# board.net
KiCad netlist of a schematic drawn in EAGLE
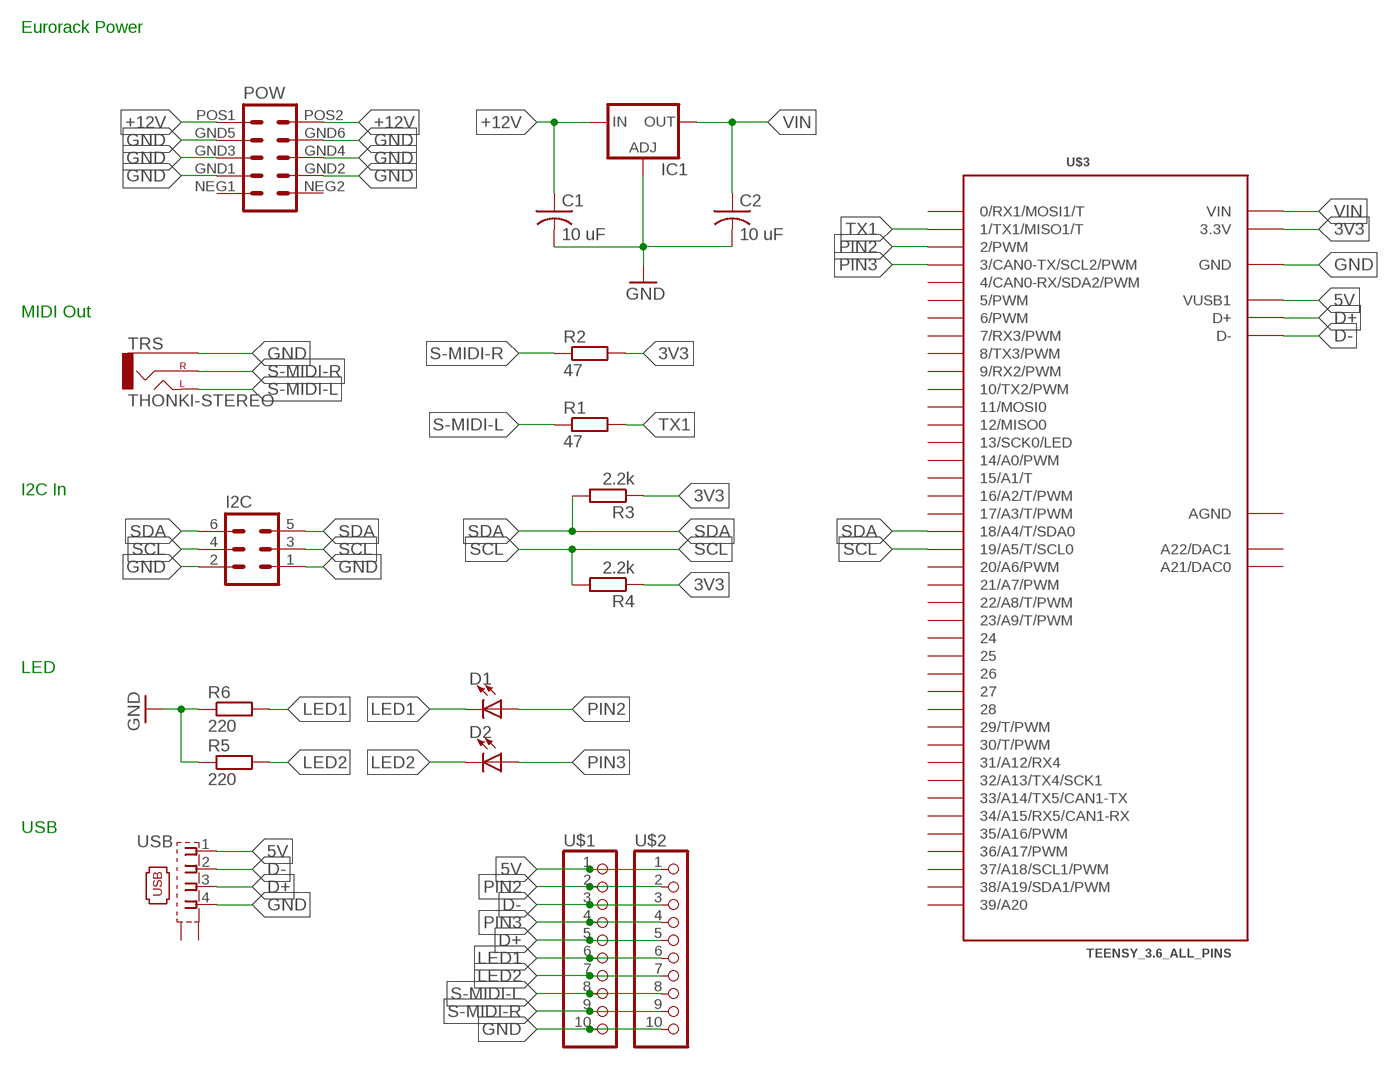
[diagram p0: schematic, sheet 1]

(export (version "E")
  (design (tool "Eeschema 10.0.6"))
  (components
    (comp (ref "C1")
      (value "10 uF")
      (footprint "eagle-import:C050-025X075")
      (libsource (lib "eagle-import") (part "C-US050-025X075"))
    )
    (comp (ref "C2")
      (value "10 uF")
      (footprint "eagle-import:C050-025X075")
      (libsource (lib "eagle-import") (part "C-US050-025X075"))
    )
    (comp (ref "D1")
      (value "LED3MM")
      (footprint "eagle-import:LED3MM")
      (libsource (lib "eagle-import") (part "LED3MM"))
    )
    (comp (ref "D2")
      (value "LED3MM")
      (footprint "eagle-import:LED3MM")
      (libsource (lib "eagle-import") (part "LED3MM"))
    )
    (comp (ref "I2C")
      (value "MA03-2BACKSIDEFRONTSIDE")
      (footprint "eagle-import:MA03-2")
      (libsource (lib "eagle-import") (part "MA03-2BACKSIDEFRONTSIDE"))
    )
    (comp (ref "IC1")
      (value "LD117AS50TR")
      (footprint "eagle-import:SOT223")
      (libsource (lib "eagle-import") (part "LD117A?S50TR"))
    )
    (comp (ref "POW")
      (value "EURO_POWER_HEADERLOCK_PADS")
      (footprint "eagle-import:EURO_PWR_HEADER_LOCK")
      (libsource (lib "eagle-import") (part "EURO_POWER_HEADERLOCK_PADS"))
    )
    (comp (ref "R1")
      (value "47")
      (footprint "eagle-import:10MM_RESISTOR")
      (libsource (lib "eagle-import") (part "RESISTOR10MM_RESISTOR"))
    )
    (comp (ref "R2")
      (value "47")
      (footprint "eagle-import:10MM_RESISTOR")
      (libsource (lib "eagle-import") (part "RESISTOR10MM_RESISTOR"))
    )
    (comp (ref "R3")
      (value "2.2k")
      (footprint "eagle-import:10MM_RESISTOR")
      (libsource (lib "eagle-import") (part "RESISTOR10MM_RESISTOR"))
    )
    (comp (ref "R4")
      (value "2.2k")
      (footprint "eagle-import:10MM_RESISTOR")
      (libsource (lib "eagle-import") (part "RESISTOR10MM_RESISTOR"))
    )
    (comp (ref "R5")
      (value "220")
      (footprint "eagle-import:10MM_RESISTOR")
      (libsource (lib "eagle-import") (part "RESISTOR10MM_RESISTOR"))
    )
    (comp (ref "R6")
      (value "220")
      (footprint "eagle-import:10MM_RESISTOR")
      (libsource (lib "eagle-import") (part "RESISTOR10MM_RESISTOR"))
    )
    (comp (ref "TRS")
      (value "THONKI-STEREO")
      (footprint "eagle-import:WQP-PJ366ST_JACK")
      (libsource (lib "eagle-import") (part "THONKI-STEREO"))
    )
    (comp (ref "U$1")
      (value "PINHD-1X10")
      (footprint "eagle-import:1X10-BIG")
      (libsource (lib "eagle-import") (part "PINHD-1X10"))
    )
    (comp (ref "U$2")
      (value "PINHD-1X10")
      (footprint "eagle-import:1X10-BIG")
      (libsource (lib "eagle-import") (part "PINHD-1X10"))
    )
    (comp (ref "U$3")
      (value "TEENSY_3.6_ALL_PINS")
      (footprint "eagle-import:TEENSY_3.6_ALL_PINS")
      (libsource (lib "eagle-import") (part "TEENSY_3.6_ALL_PINS"))
    )
    (comp (ref "USB")
      (value "KUSBVX")
      (footprint "eagle-import:KUSBVX")
      (libsource (lib "eagle-import") (part "KUSBVX"))
    )
  )
  (nets
    (net (code "1") (name "+12V") (class "Default")
      (node (ref "C1") (pin "1") (pinfunction "1_1") (pintype "passive"))
      (node (ref "IC1") (pin "3") (pinfunction "IN_3") (pintype "input"))
      (node (ref "POW") (pin "POS1") (pinfunction "10_POS1") (pintype "passive"))
      (node (ref "POW") (pin "POS2") (pinfunction "9_POS2") (pintype "passive"))
    )
    (net (code "2") (name "/AGND") (class "Default")
      (node (ref "U$3") (pin "AGND") (pinfunction "AGND_AGND") (pintype "power_in"))
    )
    (net (code "3") (name "3V3") (class "Default")
      (node (ref "R2") (pin "2") (pinfunction "2_2") (pintype "passive"))
      (node (ref "R3") (pin "1") (pinfunction "1_1") (pintype "passive"))
      (node (ref "R4") (pin "1") (pinfunction "1_1") (pintype "passive"))
      (node (ref "U$3") (pin "3.3V") (pinfunction "3.3V_3.3V") (pintype "power_in"))
      (node (ref "U$3") (pin "3.3V3") (pinfunction "3.3V_3.3V3") (pintype "power_in"))
    )
    (net (code "4") (name "5V") (class "Default")
      (node (ref "U$1") (pin "1") (pinfunction "1_1") (pintype "passive"))
      (node (ref "U$2") (pin "1") (pinfunction "1_1") (pintype "passive"))
      (node (ref "U$3") (pin "VUSB1") (pinfunction "VUSB1_VUSB1") (pintype "power_in"))
      (node (ref "USB") (pin "1") (pinfunction "1_1") (pintype "passive"))
    )
    (net (code "5") (name "D+") (class "Default")
      (node (ref "U$1") (pin "5") (pinfunction "5_5") (pintype "passive"))
      (node (ref "U$2") (pin "5") (pinfunction "5_5") (pintype "passive"))
      (node (ref "U$3") (pin "D+") (pinfunction "D+_D+") (pintype "bidirectional"))
      (node (ref "USB") (pin "3") (pinfunction "3_3") (pintype "passive"))
    )
    (net (code "6") (name "D-") (class "Default")
      (node (ref "U$1") (pin "3") (pinfunction "3_3") (pintype "passive"))
      (node (ref "U$2") (pin "3") (pinfunction "3_3") (pintype "passive"))
      (node (ref "U$3") (pin "D-") (pinfunction "D-_D-") (pintype "bidirectional"))
      (node (ref "USB") (pin "2") (pinfunction "2_2") (pintype "passive"))
    )
    (net (code "7") (name "GND") (class "Default")
      (node (ref "C1") (pin "2") (pinfunction "2_2") (pintype "passive"))
      (node (ref "C2") (pin "2") (pinfunction "2_2") (pintype "passive"))
      (node (ref "I2C") (pin "1") (pinfunction "1_1") (pintype "passive"))
      (node (ref "I2C") (pin "2") (pinfunction "2_2") (pintype "passive"))
      (node (ref "IC1") (pin "1") (pinfunction "ADJ_1") (pintype "input"))
      (node (ref "POW") (pin "GND1") (pinfunction "4_GND1") (pintype "passive"))
      (node (ref "POW") (pin "GND2") (pinfunction "3_GND2") (pintype "passive"))
      (node (ref "POW") (pin "GND3") (pinfunction "6_GND3") (pintype "passive"))
      (node (ref "POW") (pin "GND4") (pinfunction "5_GND4") (pintype "passive"))
      (node (ref "POW") (pin "GND5") (pinfunction "8_GND5") (pintype "passive"))
      (node (ref "POW") (pin "GND6") (pinfunction "7_GND6") (pintype "passive"))
      (node (ref "R5") (pin "1") (pinfunction "1_1") (pintype "passive"))
      (node (ref "R6") (pin "1") (pinfunction "1_1") (pintype "passive"))
      (node (ref "TRS") (pin "P$3_SLEEVE") (pinfunction "SLEEVE_P$3_SLEEVE") (pintype "bidirectional"))
      (node (ref "U$1") (pin "10") (pinfunction "10_10") (pintype "passive"))
      (node (ref "U$2") (pin "10") (pinfunction "10_10") (pintype "passive"))
      (node (ref "U$3") (pin "GND") (pinfunction "GND_GND") (pintype "power_in"))
      (node (ref "U$3") (pin "GND1") (pinfunction "GND_GND1") (pintype "power_in"))
      (node (ref "U$3") (pin "GND3") (pinfunction "GND_GND3") (pintype "power_in"))
      (node (ref "U$3") (pin "GND4") (pinfunction "GND_GND4") (pintype "power_in"))
      (node (ref "USB") (pin "4") (pinfunction "4_4") (pintype "passive"))
    )
    (net (code "8") (name "LED1") (class "Default")
      (node (ref "D1") (pin "K") (pinfunction "C_K") (pintype "passive"))
      (node (ref "R6") (pin "2") (pinfunction "2_2") (pintype "passive"))
      (node (ref "U$1") (pin "6") (pinfunction "6_6") (pintype "passive"))
      (node (ref "U$2") (pin "6") (pinfunction "6_6") (pintype "passive"))
    )
    (net (code "9") (name "LED2") (class "Default")
      (node (ref "D2") (pin "K") (pinfunction "C_K") (pintype "passive"))
      (node (ref "R5") (pin "2") (pinfunction "2_2") (pintype "passive"))
      (node (ref "U$1") (pin "7") (pinfunction "7_7") (pintype "passive"))
      (node (ref "U$2") (pin "7") (pinfunction "7_7") (pintype "passive"))
    )
    (net (code "10") (name "PIN2") (class "Default")
      (node (ref "D1") (pin "A") (pinfunction "A_A") (pintype "passive"))
      (node (ref "U$1") (pin "2") (pinfunction "2_2") (pintype "passive"))
      (node (ref "U$2") (pin "2") (pinfunction "2_2") (pintype "passive"))
      (node (ref "U$3") (pin "2") (pinfunction "2/PWM_2") (pintype "bidirectional"))
    )
    (net (code "11") (name "PIN3") (class "Default")
      (node (ref "D2") (pin "A") (pinfunction "A_A") (pintype "passive"))
      (node (ref "U$1") (pin "4") (pinfunction "4_4") (pintype "passive"))
      (node (ref "U$2") (pin "4") (pinfunction "4_4") (pintype "passive"))
      (node (ref "U$3") (pin "3") (pinfunction "3/CAN0-TX/SCL2/PWM_3") (pintype "bidirectional"))
    )
    (net (code "12") (name "S-MIDI-L") (class "Default")
      (node (ref "R1") (pin "1") (pinfunction "1_1") (pintype "passive"))
      (node (ref "TRS") (pin "P$1_TIP") (pinfunction "LEFT_P$1_TIP") (pintype "bidirectional"))
      (node (ref "U$1") (pin "8") (pinfunction "8_8") (pintype "passive"))
      (node (ref "U$2") (pin "8") (pinfunction "8_8") (pintype "passive"))
    )
    (net (code "13") (name "S-MIDI-R") (class "Default")
      (node (ref "R2") (pin "1") (pinfunction "1_1") (pintype "passive"))
      (node (ref "TRS") (pin "P$2_SWITCH") (pinfunction "RIGHT_P$2_SWITCH") (pintype "bidirectional"))
      (node (ref "U$1") (pin "9") (pinfunction "9_9") (pintype "passive"))
      (node (ref "U$2") (pin "9") (pinfunction "9_9") (pintype "passive"))
    )
    (net (code "14") (name "SCL") (class "Default")
      (node (ref "I2C") (pin "3") (pinfunction "3_3") (pintype "passive"))
      (node (ref "I2C") (pin "4") (pinfunction "4_4") (pintype "passive"))
      (node (ref "R4") (pin "2") (pinfunction "2_2") (pintype "passive"))
      (node (ref "U$3") (pin "19/A5") (pinfunction "19/A5/T/SCL0_19/A5") (pintype "bidirectional"))
    )
    (net (code "15") (name "SDA") (class "Default")
      (node (ref "I2C") (pin "5") (pinfunction "5_5") (pintype "passive"))
      (node (ref "I2C") (pin "6") (pinfunction "6_6") (pintype "passive"))
      (node (ref "R3") (pin "2") (pinfunction "2_2") (pintype "passive"))
      (node (ref "U$3") (pin "18/A4") (pinfunction "18/A4/T/SDA0_18/A4") (pintype "bidirectional"))
    )
    (net (code "16") (name "TX1") (class "Default")
      (node (ref "R1") (pin "2") (pinfunction "2_2") (pintype "passive"))
      (node (ref "U$3") (pin "1") (pinfunction "1/TX1/MISO1/T_1") (pintype "bidirectional"))
    )
    (net (code "17") (name "VIN") (class "Default")
      (node (ref "C2") (pin "1") (pinfunction "1_1") (pintype "passive"))
      (node (ref "IC1") (pin "2") (pinfunction "OUT_2") (pintype "passive"))
      (node (ref "IC1") (pin "4") (pinfunction "OUT_4") (pintype "passive"))
      (node (ref "U$3") (pin "VIN") (pinfunction "VIN_VIN") (pintype "power_in"))
    )
    (net (code "18") (name "unconnected-(POW-1-PadNEG2)") (class "Default")
      (node (ref "POW") (pin "NEG2") (pinfunction "1_NEG2") (pintype "passive"))
    )
    (net (code "19") (name "unconnected-(POW-2-PadNEG1)") (class "Default")
      (node (ref "POW") (pin "NEG1") (pinfunction "2_NEG1") (pintype "passive"))
    )
    (net (code "20") (name "unconnected-(U$3-0{slash}RX1{slash}MOSI1{slash}T-Pad0)") (class "Default")
      (node (ref "U$3") (pin "0") (pinfunction "0/RX1/MOSI1/T_0") (pintype "bidirectional"))
    )
    (net (code "21") (name "unconnected-(U$3-4{slash}CAN0-RX{slash}SDA2{slash}PWM-Pad4)") (class "Default")
      (node (ref "U$3") (pin "4") (pinfunction "4/CAN0-RX/SDA2/PWM_4") (pintype "bidirectional"))
    )
    (net (code "22") (name "unconnected-(U$3-5{slash}PWM-Pad5)") (class "Default")
      (node (ref "U$3") (pin "5") (pinfunction "5/PWM_5") (pintype "bidirectional"))
    )
    (net (code "23") (name "unconnected-(U$3-6{slash}PWM-Pad6)") (class "Default")
      (node (ref "U$3") (pin "6") (pinfunction "6/PWM_6") (pintype "bidirectional"))
    )
    (net (code "24") (name "unconnected-(U$3-7{slash}RX3{slash}PWM-Pad7)") (class "Default")
      (node (ref "U$3") (pin "7") (pinfunction "7/RX3/PWM_7") (pintype "bidirectional"))
    )
    (net (code "25") (name "unconnected-(U$3-8{slash}TX3{slash}PWM-Pad8)") (class "Default")
      (node (ref "U$3") (pin "8") (pinfunction "8/TX3/PWM_8") (pintype "bidirectional"))
    )
    (net (code "26") (name "unconnected-(U$3-9{slash}RX2{slash}PWM-Pad9)") (class "Default")
      (node (ref "U$3") (pin "9") (pinfunction "9/RX2/PWM_9") (pintype "bidirectional"))
    )
    (net (code "27") (name "unconnected-(U$3-10{slash}TX2{slash}PWM-Pad10)") (class "Default")
      (node (ref "U$3") (pin "10") (pinfunction "10/TX2/PWM_10") (pintype "bidirectional"))
    )
    (net (code "28") (name "unconnected-(U$3-11{slash}MOSI0-Pad11)") (class "Default")
      (node (ref "U$3") (pin "11") (pinfunction "11/MOSI0_11") (pintype "bidirectional"))
    )
    (net (code "29") (name "unconnected-(U$3-12{slash}MISO0-Pad12)") (class "Default")
      (node (ref "U$3") (pin "12") (pinfunction "12/MISO0_12") (pintype "bidirectional"))
    )
    (net (code "30") (name "unconnected-(U$3-13{slash}SCK0{slash}LED-Pad13)") (class "Default")
      (node (ref "U$3") (pin "13") (pinfunction "13/SCK0/LED_13") (pintype "bidirectional"))
    )
    (net (code "31") (name "unconnected-(U$3-14{slash}A0{slash}PWM-Pad14{slash}A0)") (class "Default")
      (node (ref "U$3") (pin "14/A0") (pinfunction "14/A0/PWM_14/A0") (pintype "bidirectional"))
    )
    (net (code "32") (name "unconnected-(U$3-15{slash}A1{slash}T-Pad15{slash}A1)") (class "Default")
      (node (ref "U$3") (pin "15/A1") (pinfunction "15/A1/T_15/A1") (pintype "bidirectional"))
    )
    (net (code "33") (name "unconnected-(U$3-16{slash}A2{slash}T{slash}PWM-Pad16{slash}A2)") (class "Default")
      (node (ref "U$3") (pin "16/A2") (pinfunction "16/A2/T/PWM_16/A2") (pintype "bidirectional"))
    )
    (net (code "34") (name "unconnected-(U$3-17{slash}A3{slash}T{slash}PWM-Pad17{slash}A3)") (class "Default")
      (node (ref "U$3") (pin "17/A3") (pinfunction "17/A3/T/PWM_17/A3") (pintype "bidirectional"))
    )
    (net (code "35") (name "unconnected-(U$3-20{slash}A6{slash}PWM-Pad20{slash}A6)") (class "Default")
      (node (ref "U$3") (pin "20/A6") (pinfunction "20/A6/PWM_20/A6") (pintype "bidirectional"))
    )
    (net (code "36") (name "unconnected-(U$3-21{slash}A7{slash}PWM-Pad21{slash}A7)") (class "Default")
      (node (ref "U$3") (pin "21/A7") (pinfunction "21/A7/PWM_21/A7") (pintype "bidirectional"))
    )
    (net (code "37") (name "unconnected-(U$3-22{slash}A8{slash}T{slash}PWM-Pad22{slash}A8)") (class "Default")
      (node (ref "U$3") (pin "22/A8") (pinfunction "22/A8/T/PWM_22/A8") (pintype "bidirectional"))
    )
    (net (code "38") (name "unconnected-(U$3-23{slash}A9{slash}T{slash}PWM-Pad23{slash}A9)") (class "Default")
      (node (ref "U$3") (pin "23/A9") (pinfunction "23/A9/T/PWM_23/A9") (pintype "bidirectional"))
    )
    (net (code "39") (name "unconnected-(U$3-29{slash}T{slash}PWM-Pad29)") (class "Default")
      (node (ref "U$3") (pin "29") (pinfunction "29/T/PWM_29") (pintype "bidirectional"))
    )
    (net (code "40") (name "unconnected-(U$3-30{slash}T{slash}PWM-Pad30)") (class "Default")
      (node (ref "U$3") (pin "30") (pinfunction "30/T/PWM_30") (pintype "bidirectional"))
    )
    (net (code "41") (name "unconnected-(U$3-31{slash}A12{slash}RX4-Pad31{slash}A12)") (class "Default")
      (node (ref "U$3") (pin "31/A12") (pinfunction "31/A12/RX4_31/A12") (pintype "bidirectional"))
    )
    (net (code "42") (name "unconnected-(U$3-32{slash}A13{slash}TX4{slash}SCK1-Pad32{slash}A13)") (class "Default")
      (node (ref "U$3") (pin "32/A13") (pinfunction "32/A13/TX4/SCK1_32/A13") (pintype "bidirectional"))
    )
    (net (code "43") (name "unconnected-(U$3-33{slash}A14{slash}TX5{slash}CAN1-TX-Pad33{slash}A14)") (class "Default")
      (node (ref "U$3") (pin "33/A14") (pinfunction "33/A14/TX5/CAN1-TX_33/A14") (pintype "bidirectional"))
    )
    (net (code "44") (name "unconnected-(U$3-34{slash}A15{slash}RX5{slash}CAN1-RX-Pad34{slash}A15)") (class "Default")
      (node (ref "U$3") (pin "34/A15") (pinfunction "34/A15/RX5/CAN1-RX_34/A15") (pintype "bidirectional"))
    )
    (net (code "45") (name "unconnected-(U$3-35{slash}A16{slash}PWM-Pad35{slash}A16)") (class "Default")
      (node (ref "U$3") (pin "35/A16") (pinfunction "35/A16/PWM_35/A16") (pintype "bidirectional"))
    )
    (net (code "46") (name "unconnected-(U$3-36{slash}A17{slash}PWM-Pad36{slash}A17)") (class "Default")
      (node (ref "U$3") (pin "36/A17") (pinfunction "36/A17/PWM_36/A17") (pintype "bidirectional"))
    )
    (net (code "47") (name "unconnected-(U$3-37{slash}A18{slash}SCL1{slash}PWM-Pad37{slash}A18)") (class "Default")
      (node (ref "U$3") (pin "37/A18") (pinfunction "37/A18/SCL1/PWM_37/A18") (pintype "bidirectional"))
    )
    (net (code "48") (name "unconnected-(U$3-38{slash}A19{slash}SDA1{slash}PWM-Pad38{slash}A19)") (class "Default")
      (node (ref "U$3") (pin "38/A19") (pinfunction "38/A19/SDA1/PWM_38/A19") (pintype "bidirectional"))
    )
    (net (code "49") (name "unconnected-(U$3-A21{slash}DAC0-PadA21)") (class "Default")
      (node (ref "U$3") (pin "A21") (pinfunction "A21/DAC0_A21") (pintype "bidirectional"))
    )
    (net (code "50") (name "unconnected-(U$3-A22{slash}DAC1-PadA22)") (class "Default")
      (node (ref "U$3") (pin "A22") (pinfunction "A22/DAC1_A22") (pintype "bidirectional"))
    )
    (net (code "51") (name "unconnected-(U$3-Pad24)") (class "Default")
      (node (ref "U$3") (pin "24") (pinfunction "24_24") (pintype "bidirectional"))
    )
    (net (code "52") (name "unconnected-(U$3-Pad25)") (class "Default")
      (node (ref "U$3") (pin "25") (pinfunction "25_25") (pintype "bidirectional"))
    )
    (net (code "53") (name "unconnected-(U$3-Pad26)") (class "Default")
      (node (ref "U$3") (pin "26") (pinfunction "26_26") (pintype "bidirectional"))
    )
    (net (code "54") (name "unconnected-(U$3-Pad27)") (class "Default")
      (node (ref "U$3") (pin "27") (pinfunction "27_27") (pintype "bidirectional"))
    )
    (net (code "55") (name "unconnected-(U$3-Pad28)") (class "Default")
      (node (ref "U$3") (pin "28") (pinfunction "28_28") (pintype "bidirectional"))
    )
    (net (code "56") (name "unconnected-(U$3-Pad39{slash}A20)") (class "Default")
      (node (ref "U$3") (pin "39/A20") (pinfunction "39/A20_39/A20") (pintype "bidirectional"))
    )
    (net (code "57") (name "unconnected-(USB-S1-PadM1)") (class "Default")
      (node (ref "USB") (pin "M1") (pinfunction "S1_M1") (pintype "passive"))
    )
    (net (code "58") (name "unconnected-(USB-S2-PadM2)") (class "Default")
      (node (ref "USB") (pin "M2") (pinfunction "S2_M2") (pintype "passive"))
    )
  )
)
